# MCU.net
KiCad netlist of a schematic drawn in Altium Designer
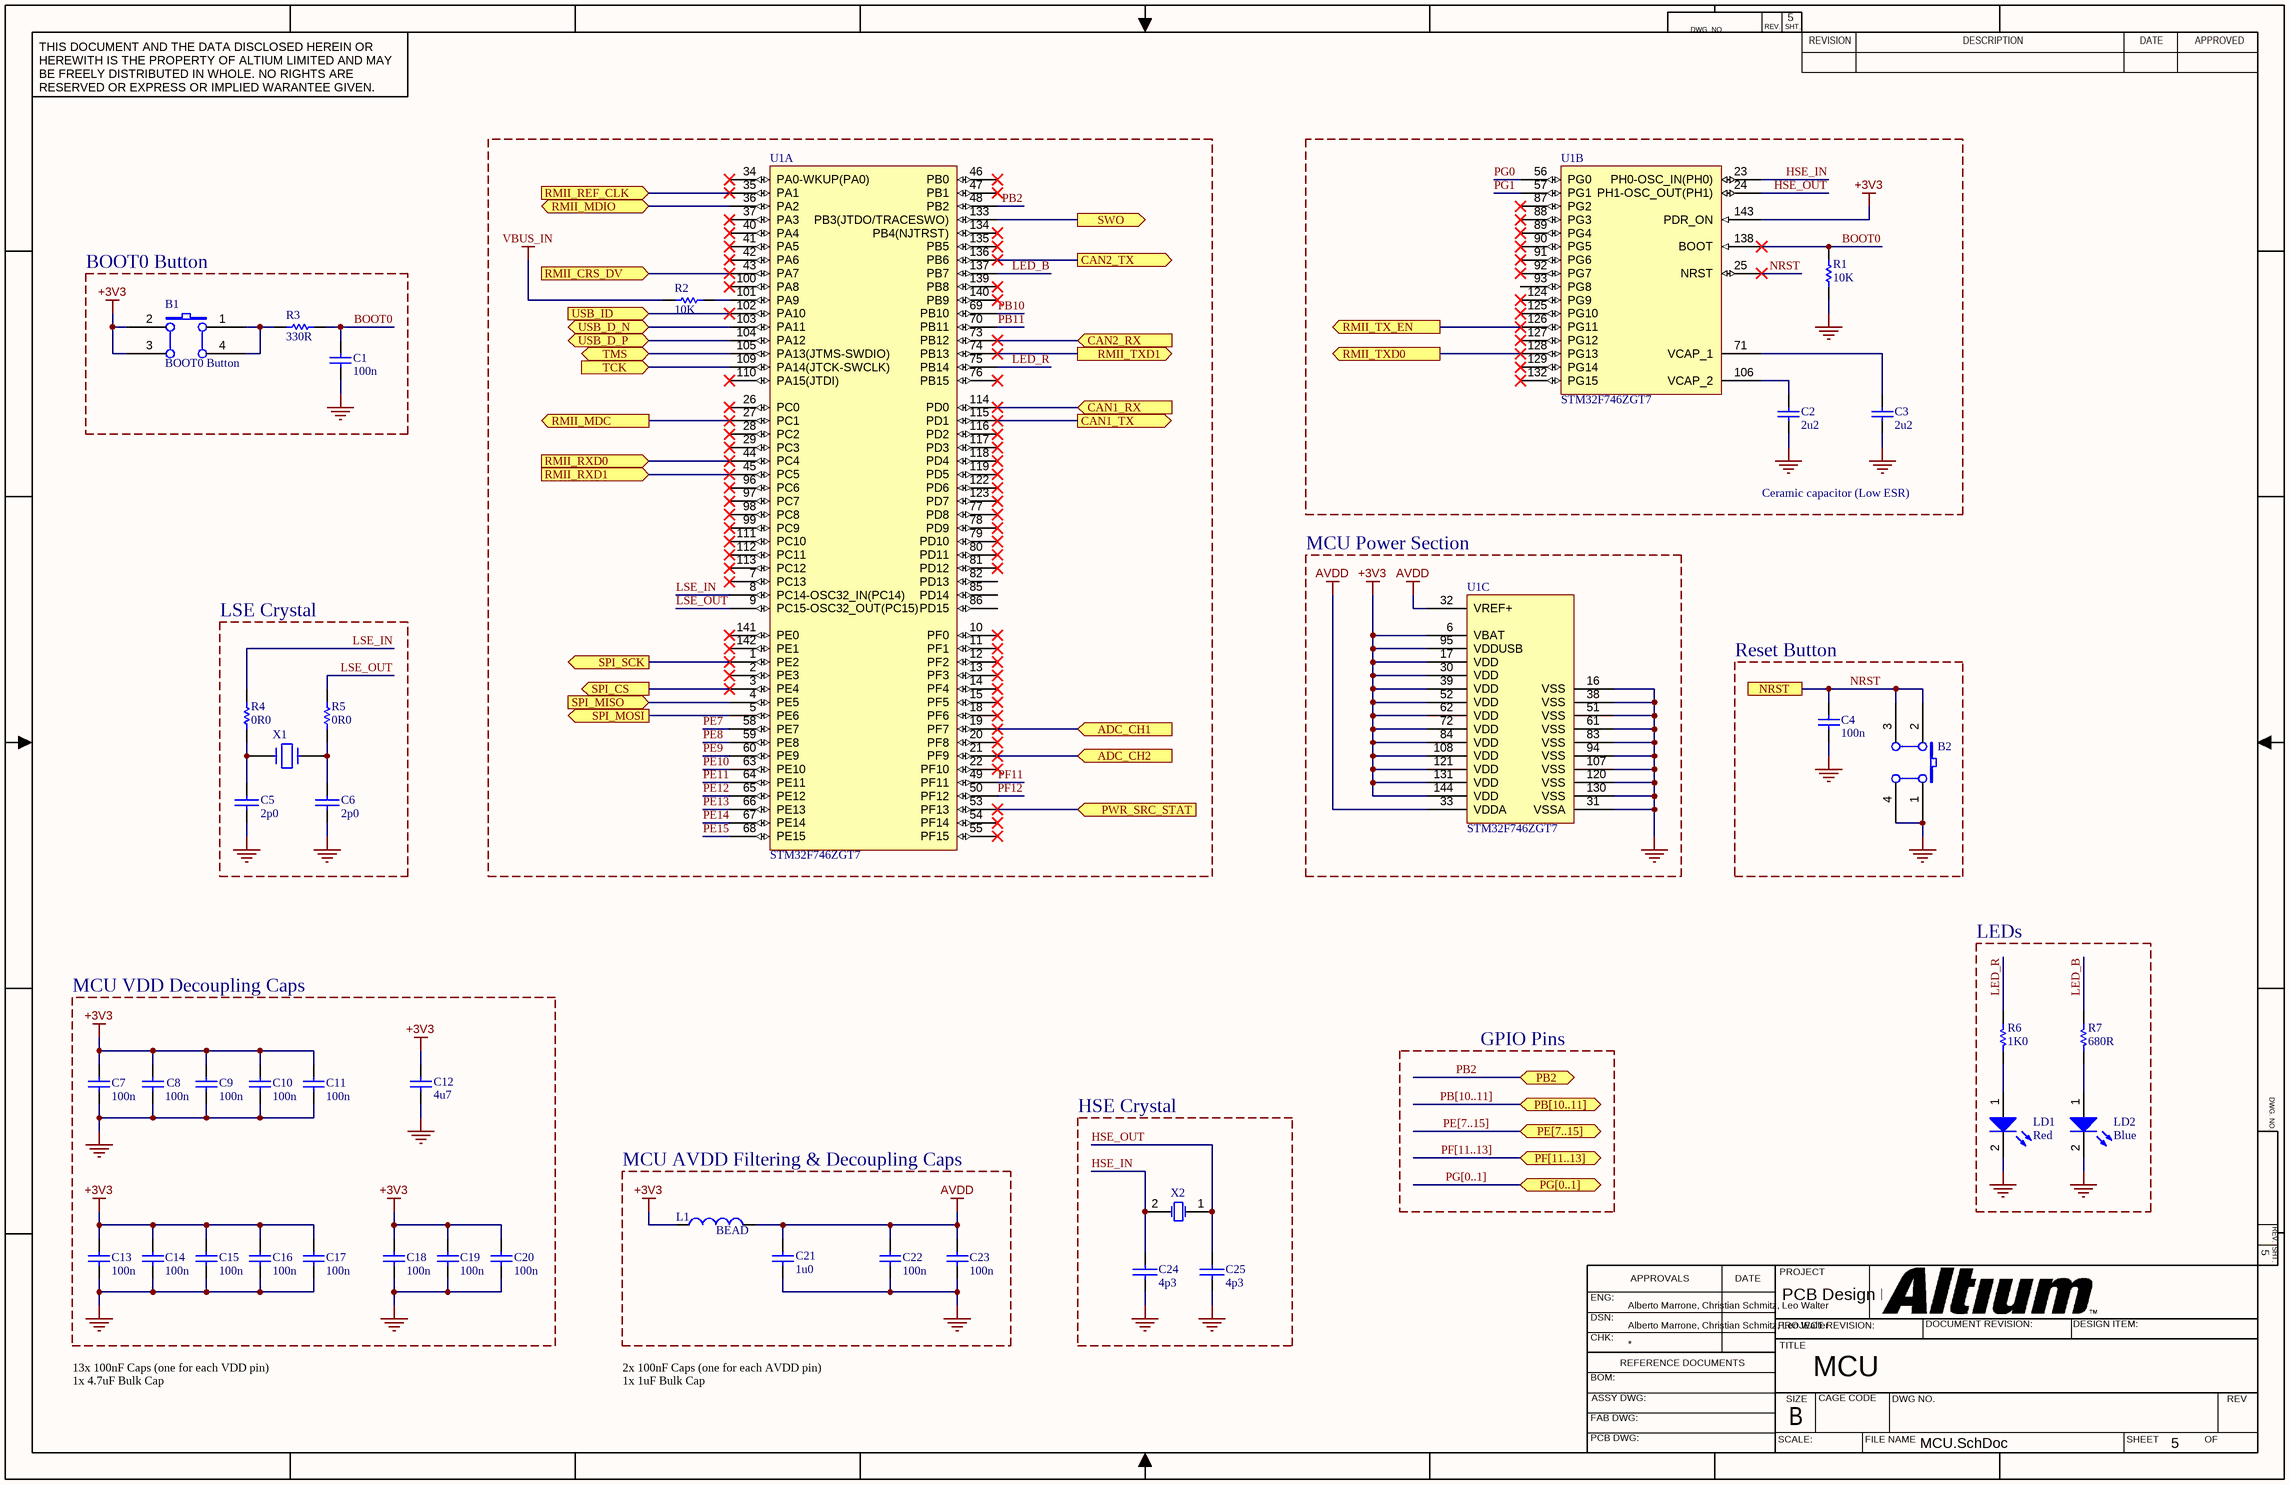
[diagram p0: MCU.SchDoc]

(export (version "E")
  (design (tool "Eeschema 10.0.6"))
  (components
    (comp (ref "B1")
      (value "BOOT0 Button")
      (footprint "PB-6X6mm-Blue")
      (description "SE PUSHBUTTON")
      (libsource (lib "Documents") (part "SW PUSHBUTTON"))
    )
    (comp (ref "B2")
      (value "TS40-66-33-BK-160-SMT-TR")
      (footprint "PB-6X6mm-Black")
      (description "SE PUSHBUTTON")
      (libsource (lib "Documents") (part "SW PUSHBUTTON"))
    )
    (comp (ref "C1")
      (value "100n")
      (footprint "0603C")
      (description "Capacitor")
      (fields (field (name "PUBLISHER") "Altium Limited"))
      (libsource (lib "Miscellaneous Devices") (part "Cap"))
    )
    (comp (ref "C2")
      (value "2u2")
      (footprint "TAN-A")
      (description "Capacitor,2.2uF,16V, X7R,10%,0805,YAGEO")
      (libsource (lib "MCD_TOOLS") (part "Cap_2.2uF_X7R_10%_0805"))
    )
    (comp (ref "C3")
      (value "2u2")
      (footprint "TAN-A")
      (description "Capacitor,2.2uF,16V, X7R,10%,0805,YAGEO")
      (libsource (lib "MCD_TOOLS") (part "Cap_2.2uF_X7R_10%_0805"))
    )
    (comp (ref "C4")
      (value "100n")
      (footprint "0603C")
      (description "Capacitor")
      (fields (field (name "PUBLISHER") "Altium Limited"))
      (libsource (lib "Miscellaneous Devices") (part "Cap"))
    )
    (comp (ref "C5")
      (value "2p0")
      (footprint "0603C")
      (description "Capacitor")
      (libsource (lib "") (part "CAP_1"))
    )
    (comp (ref "C6")
      (value "2p0")
      (footprint "0603C")
      (description "Capacitor")
      (libsource (lib "") (part "CAP_1"))
    )
    (comp (ref "C7")
      (value "100n")
      (footprint "0603C")
      (description "Capacitor")
      (fields (field (name "PUBLISHER") "Altium Limited"))
      (libsource (lib "Miscellaneous Devices") (part "Cap"))
    )
    (comp (ref "C8")
      (value "100n")
      (footprint "0603C")
      (description "Capacitor")
      (fields (field (name "PUBLISHER") "Altium Limited"))
      (libsource (lib "Miscellaneous Devices") (part "Cap"))
    )
    (comp (ref "C9")
      (value "100n")
      (footprint "0603C")
      (description "Capacitor")
      (fields (field (name "PUBLISHER") "Altium Limited"))
      (libsource (lib "Miscellaneous Devices") (part "Cap"))
    )
    (comp (ref "C10")
      (value "100n")
      (footprint "0603C")
      (description "Capacitor")
      (fields (field (name "PUBLISHER") "Altium Limited"))
      (libsource (lib "Miscellaneous Devices") (part "Cap"))
    )
    (comp (ref "C11")
      (value "100n")
      (footprint "0603C")
      (description "Capacitor")
      (fields (field (name "PUBLISHER") "Altium Limited"))
      (libsource (lib "Miscellaneous Devices") (part "Cap"))
    )
    (comp (ref "C12")
      (value "4u7")
      (footprint "0603C")
      (description "Capacitor")
      (fields (field (name "TOLERANCE") "10%"))
      (libsource (lib "MB963_1") (part "CAP SMD 0603  X5R 1µF 25V 10%"))
    )
    (comp (ref "C13")
      (value "100n")
      (footprint "0603C")
      (description "Capacitor")
      (fields (field (name "PUBLISHER") "Altium Limited"))
      (libsource (lib "Miscellaneous Devices") (part "Cap"))
    )
    (comp (ref "C14")
      (value "100n")
      (footprint "0603C")
      (description "Capacitor")
      (fields (field (name "PUBLISHER") "Altium Limited"))
      (libsource (lib "Miscellaneous Devices") (part "Cap"))
    )
    (comp (ref "C15")
      (value "100n")
      (footprint "0603C")
      (description "Capacitor")
      (fields (field (name "PUBLISHER") "Altium Limited"))
      (libsource (lib "Miscellaneous Devices") (part "Cap"))
    )
    (comp (ref "C16")
      (value "100n")
      (footprint "0603C")
      (description "Capacitor")
      (fields (field (name "PUBLISHER") "Altium Limited"))
      (libsource (lib "Miscellaneous Devices") (part "Cap"))
    )
    (comp (ref "C17")
      (value "100n")
      (footprint "0603C")
      (description "Capacitor")
      (fields (field (name "PUBLISHER") "Altium Limited"))
      (libsource (lib "Miscellaneous Devices") (part "Cap"))
    )
    (comp (ref "C18")
      (value "100n")
      (footprint "0603C")
      (description "Capacitor")
      (fields (field (name "PUBLISHER") "Altium Limited"))
      (libsource (lib "Miscellaneous Devices") (part "Cap"))
    )
    (comp (ref "C19")
      (value "100n")
      (footprint "0603C")
      (description "Capacitor")
      (fields (field (name "PUBLISHER") "Altium Limited"))
      (libsource (lib "Miscellaneous Devices") (part "Cap"))
    )
    (comp (ref "C20")
      (value "100n")
      (footprint "0603C")
      (description "Capacitor")
      (fields (field (name "PUBLISHER") "Altium Limited"))
      (libsource (lib "Miscellaneous Devices") (part "Cap"))
    )
    (comp (ref "C21")
      (value "1u0")
      (footprint "0603C")
      (description "Capacitor")
      (fields (field (name "TOLERANCE") "10%"))
      (libsource (lib "MB963_1") (part "CAP SMD 0603  X5R 1µF 25V 10%"))
    )
    (comp (ref "C22")
      (value "100n")
      (footprint "0603C")
      (description "Capacitor")
      (fields (field (name "PUBLISHER") "Altium Limited"))
      (libsource (lib "Miscellaneous Devices") (part "Cap"))
    )
    (comp (ref "C23")
      (value "100n")
      (footprint "0603C")
      (description "Capacitor")
      (fields (field (name "PUBLISHER") "Altium Limited"))
      (libsource (lib "Miscellaneous Devices") (part "Cap"))
    )
    (comp (ref "C24")
      (value "4p3")
      (footprint "0603C")
      (description "Capacitor")
      (libsource (lib "*") (part "CAP"))
    )
    (comp (ref "C25")
      (value "4p3")
      (footprint "0603C")
      (description "Capacitor")
      (libsource (lib "*") (part "CAP"))
    )
    (comp (ref "L1")
      (value "BEAD")
      (footprint "0603L")
      (description "Inductor")
      (fields (field (name "PUBLISHER") "Altium Limited"))
      (libsource (lib "Miscellaneous Devices") (part "Inductor"))
    )
    (comp (ref "LD1")
      (value "Red")
      (footprint "0603D-R")
      (description "Typical RED, GREEN, YELLOW, AMBER GaAs LED")
      (fields (field (name "PUBLISHER") "Altium Limited"))
      (libsource (lib "Miscellaneous Devices") (part "LED2"))
    )
    (comp (ref "LD2")
      (value "Blue")
      (footprint "0603D-B")
      (description "Typical RED, GREEN, YELLOW, AMBER GaAs LED")
      (fields (field (name "PUBLISHER") "Altium Limited"))
      (libsource (lib "Miscellaneous Devices") (part "LED2"))
    )
    (comp (ref "R1")
      (value "10K")
      (footprint "0603R")
      (description "Resistor")
      (fields (field (name "PUBLISHER") "Altium Limited"))
      (libsource (lib "Miscellaneous Devices") (part "res1"))
    )
    (comp (ref "R2")
      (value "10K")
      (footprint "0603R")
      (description "Resistor")
      (fields (field (name "PUBLISHER") "Altium Limited"))
      (libsource (lib "Miscellaneous Devices") (part "res1"))
    )
    (comp (ref "R3")
      (value "330R")
      (footprint "0603R")
      (description "Resistor")
      (fields (field (name "PUBLISHER") "Altium Limited"))
      (libsource (lib "Miscellaneous Devices") (part "Res1"))
    )
    (comp (ref "R4")
      (value "0R0")
      (footprint "0603R")
      (description "Resistor")
      (fields (field (name "PUBLISHER") "Altium Limited"))
      (libsource (lib "Miscellaneous Devices") (part "Res1"))
    )
    (comp (ref "R5")
      (value "0R0")
      (footprint "0603R")
      (description "Resistor")
      (fields (field (name "PUBLISHER") "Altium Limited"))
      (libsource (lib "Miscellaneous Devices") (part "Res1"))
    )
    (comp (ref "R6")
      (value "1K0")
      (footprint "0603R")
      (description "Resistor")
      (fields (field (name "PUBLISHER") "Altium Limited"))
      (libsource (lib "Miscellaneous Devices") (part "Res1"))
    )
    (comp (ref "R7")
      (value "680R")
      (footprint "0603R")
      (description "Resistor")
      (fields (field (name "PUBLISHER") "Altium Limited"))
      (libsource (lib "Miscellaneous Devices") (part "Res1"))
    )
    (comp (ref "U1")
      (value "STM32F746ZGT7")
      (footprint "STM-LQFP144_M")
      (libsource (lib "Altium Content Vault") (part "MC-ARM-STM32F7X6-LQFP144"))
    )
    (comp (ref "X1")
      (value "ABS07-120-32.768KHZ-T")
      (footprint "XTAL_2SM_3R2X1R5")
      (description "Crystal")
      (libsource (lib "MB1167") (part "CRYSTAL_32K"))
    )
    (comp (ref "X2")
      (value "ABM8AAIG-8.000MHz-V2R-T3")
      (footprint "OSC_2SM_3R2x2R5")
      (description "Crystal Oscillator")
      (fields (field (name "PUBLISHER") "Altium Limited"))
      (libsource (lib "MB963_1") (part "XTAL"))
    )
  )
  (nets
    (net (code "2") (name "+3V3") (class "Default")
      (node (ref "B1") (pin "2") (pinfunction "B0_2") (pintype "passive"))
      (node (ref "B1") (pin "3") (pinfunction "B1_3") (pintype "passive"))
      (node (ref "C10") (pin "1") (pinfunction "1_1") (pintype "passive"))
      (node (ref "C11") (pin "1") (pinfunction "1_1") (pintype "passive"))
      (node (ref "C12") (pin "1") (pinfunction "1_1") (pintype "passive"))
      (node (ref "C13") (pin "1") (pinfunction "1_1") (pintype "passive"))
      (node (ref "C14") (pin "1") (pinfunction "1_1") (pintype "passive"))
      (node (ref "C15") (pin "1") (pinfunction "1_1") (pintype "passive"))
      (node (ref "C16") (pin "1") (pinfunction "1_1") (pintype "passive"))
      (node (ref "C17") (pin "1") (pinfunction "1_1") (pintype "passive"))
      (node (ref "C18") (pin "1") (pinfunction "1_1") (pintype "passive"))
      (node (ref "C19") (pin "1") (pinfunction "1_1") (pintype "passive"))
      (node (ref "C20") (pin "1") (pinfunction "1_1") (pintype "passive"))
      (node (ref "C7") (pin "1") (pinfunction "1_1") (pintype "passive"))
      (node (ref "C8") (pin "1") (pinfunction "1_1") (pintype "passive"))
      (node (ref "C9") (pin "1") (pinfunction "1_1") (pintype "passive"))
      (node (ref "L1") (pin "1") (pinfunction "1_1") (pintype "passive"))
      (node (ref "U1") (pin "108") (pinfunction "VDD_108") (pintype "power_in"))
      (node (ref "U1") (pin "121") (pinfunction "VDD_121") (pintype "power_in"))
      (node (ref "U1") (pin "131") (pinfunction "VDD_131") (pintype "power_in"))
      (node (ref "U1") (pin "143") (pinfunction "PDR_ON_143") (pintype "input"))
      (node (ref "U1") (pin "144") (pinfunction "VDD_144") (pintype "power_in"))
      (node (ref "U1") (pin "17") (pinfunction "VDD_17") (pintype "power_in"))
      (node (ref "U1") (pin "30") (pinfunction "VDD_30") (pintype "power_in"))
      (node (ref "U1") (pin "39") (pinfunction "VDD_39") (pintype "power_in"))
      (node (ref "U1") (pin "52") (pinfunction "VDD_52") (pintype "power_in"))
      (node (ref "U1") (pin "6") (pinfunction "VBAT_6") (pintype "power_in"))
      (node (ref "U1") (pin "62") (pinfunction "VDD_62") (pintype "power_in"))
      (node (ref "U1") (pin "72") (pinfunction "VDD_72") (pintype "power_in"))
      (node (ref "U1") (pin "84") (pinfunction "VDD_84") (pintype "power_in"))
      (node (ref "U1") (pin "95") (pinfunction "VDDUSB_95") (pintype "power_in"))
    )
    (net (code "3") (name "/ADC_CH1") (class "Default")
      (node (ref "U1") (pin "19") (pinfunction "PF7_19") (pintype "bidirectional+no_connect"))
    )
    (net (code "4") (name "/ADC_CH2") (class "Default")
      (node (ref "U1") (pin "21") (pinfunction "PF9_21") (pintype "bidirectional+no_connect"))
    )
    (net (code "5") (name "/BOOT0") (class "Default")
      (node (ref "C1") (pin "2") (pinfunction "2_2") (pintype "passive"))
      (node (ref "R1") (pin "1") (pinfunction "1_1") (pintype "passive"))
      (node (ref "R3") (pin "2") (pinfunction "2_2") (pintype "passive"))
      (node (ref "U1") (pin "138") (pinfunction "BOOT_138") (pintype "input"))
    )
    (net (code "6") (name "/CAN1_RX") (class "Default")
      (node (ref "U1") (pin "114") (pinfunction "PD0_114") (pintype "bidirectional+no_connect"))
    )
    (net (code "7") (name "/CAN1_TX") (class "Default")
      (node (ref "U1") (pin "115") (pinfunction "PD1_115") (pintype "bidirectional+no_connect"))
    )
    (net (code "8") (name "/CAN2_RX") (class "Default")
      (node (ref "U1") (pin "73") (pinfunction "PB12_73") (pintype "bidirectional+no_connect"))
    )
    (net (code "9") (name "/CAN2_TX") (class "Default")
      (node (ref "U1") (pin "136") (pinfunction "PB6_136") (pintype "bidirectional+no_connect"))
    )
    (net (code "10") (name "/HSE_IN") (class "Default")
      (node (ref "C24") (pin "1") (pinfunction "1_1") (pintype "passive"))
      (node (ref "U1") (pin "23") (pinfunction "PH0-OSC_IN(PH0)_23") (pintype "bidirectional"))
      (node (ref "X2") (pin "2") (pinfunction "OSC2_2") (pintype "passive"))
    )
    (net (code "11") (name "/HSE_OUT") (class "Default")
      (node (ref "C25") (pin "1") (pinfunction "1_1") (pintype "passive"))
      (node (ref "U1") (pin "24") (pinfunction "PH1-OSC_OUT(PH1)_24") (pintype "bidirectional"))
      (node (ref "X2") (pin "1") (pinfunction "OSC1_1") (pintype "passive"))
    )
    (net (code "12") (name "/LED_B") (class "Default")
      (node (ref "R7") (pin "1") (pinfunction "1_1") (pintype "passive"))
      (node (ref "U1") (pin "137") (pinfunction "PB7_137") (pintype "bidirectional"))
    )
    (net (code "13") (name "/LED_R") (class "Default")
      (node (ref "R6") (pin "1") (pinfunction "1_1") (pintype "passive"))
      (node (ref "U1") (pin "75") (pinfunction "PB14_75") (pintype "bidirectional"))
    )
    (net (code "14") (name "/LSE_IN") (class "Default")
      (node (ref "R4") (pin "2") (pinfunction "2_2") (pintype "passive"))
      (node (ref "U1") (pin "8") (pinfunction "PC14-OSC32_IN(PC14)_8") (pintype "bidirectional"))
    )
    (net (code "15") (name "/LSE_OUT") (class "Default")
      (node (ref "R5") (pin "2") (pinfunction "2_2") (pintype "passive"))
      (node (ref "U1") (pin "9") (pinfunction "PC15-OSC32_OUT(PC15)_9") (pintype "bidirectional"))
    )
    (net (code "16") (name "/NRST") (class "Default")
      (node (ref "B2") (pin "2") (pinfunction "B0_2") (pintype "passive"))
      (node (ref "B2") (pin "3") (pinfunction "B1_3") (pintype "passive"))
      (node (ref "C4") (pin "2") (pinfunction "2_2") (pintype "passive"))
      (node (ref "U1") (pin "25") (pinfunction "NRST_25") (pintype "bidirectional"))
    )
    (net (code "17") (name "/PB2") (class "Default")
      (node (ref "U1") (pin "48") (pinfunction "PB2_48") (pintype "bidirectional"))
    )
    (net (code "18") (name "/PB10") (class "Default")
      (node (ref "U1") (pin "69") (pinfunction "PB10_69") (pintype "bidirectional"))
    )
    (net (code "19") (name "/PB11") (class "Default")
      (node (ref "U1") (pin "70") (pinfunction "PB11_70") (pintype "bidirectional"))
    )
    (net (code "21") (name "/PE7") (class "Default")
      (node (ref "U1") (pin "58") (pinfunction "PE7_58") (pintype "bidirectional"))
    )
    (net (code "22") (name "/PE8") (class "Default")
      (node (ref "U1") (pin "59") (pinfunction "PE8_59") (pintype "bidirectional"))
    )
    (net (code "23") (name "/PE9") (class "Default")
      (node (ref "U1") (pin "60") (pinfunction "PE9_60") (pintype "bidirectional"))
    )
    (net (code "24") (name "/PE10") (class "Default")
      (node (ref "U1") (pin "63") (pinfunction "PE10_63") (pintype "bidirectional"))
    )
    (net (code "25") (name "/PE11") (class "Default")
      (node (ref "U1") (pin "64") (pinfunction "PE11_64") (pintype "bidirectional"))
    )
    (net (code "26") (name "/PE12") (class "Default")
      (node (ref "U1") (pin "65") (pinfunction "PE12_65") (pintype "bidirectional"))
    )
    (net (code "27") (name "/PE13") (class "Default")
      (node (ref "U1") (pin "66") (pinfunction "PE13_66") (pintype "bidirectional"))
    )
    (net (code "28") (name "/PE14") (class "Default")
      (node (ref "U1") (pin "67") (pinfunction "PE14_67") (pintype "bidirectional"))
    )
    (net (code "29") (name "/PE15") (class "Default")
      (node (ref "U1") (pin "68") (pinfunction "PE15_68") (pintype "bidirectional"))
    )
    (net (code "31") (name "/PF11") (class "Default")
      (node (ref "U1") (pin "49") (pinfunction "PF11_49") (pintype "bidirectional"))
    )
    (net (code "32") (name "/PF12") (class "Default")
      (node (ref "U1") (pin "50") (pinfunction "PF12_50") (pintype "bidirectional"))
    )
    (net (code "34") (name "/PG0") (class "Default")
      (node (ref "U1") (pin "56") (pinfunction "PG0_56") (pintype "bidirectional"))
    )
    (net (code "35") (name "/PG1") (class "Default")
      (node (ref "U1") (pin "57") (pinfunction "PG1_57") (pintype "bidirectional"))
    )
    (net (code "37") (name "/PWR_SRC_STAT") (class "Default")
      (node (ref "U1") (pin "53") (pinfunction "PF13_53") (pintype "bidirectional+no_connect"))
    )
    (net (code "38") (name "/RMII_CRS_DV") (class "Default")
      (node (ref "U1") (pin "43") (pinfunction "PA7_43") (pintype "bidirectional+no_connect"))
    )
    (net (code "39") (name "/RMII_MDC") (class "Default")
      (node (ref "U1") (pin "27") (pinfunction "PC1_27") (pintype "bidirectional+no_connect"))
    )
    (net (code "40") (name "/RMII_MDIO") (class "Default")
      (node (ref "U1") (pin "36") (pinfunction "PA2_36") (pintype "bidirectional"))
    )
    (net (code "41") (name "/RMII_REF_CLK") (class "Default")
      (node (ref "U1") (pin "35") (pinfunction "PA1_35") (pintype "bidirectional+no_connect"))
    )
    (net (code "42") (name "/RMII_RXD0") (class "Default")
      (node (ref "U1") (pin "44") (pinfunction "PC4_44") (pintype "bidirectional+no_connect"))
    )
    (net (code "43") (name "/RMII_RXD1") (class "Default")
      (node (ref "U1") (pin "45") (pinfunction "PC5_45") (pintype "bidirectional+no_connect"))
    )
    (net (code "44") (name "/RMII_TXD0") (class "Default")
      (node (ref "U1") (pin "128") (pinfunction "PG13_128") (pintype "bidirectional+no_connect"))
    )
    (net (code "45") (name "/RMII_TXD1") (class "Default")
      (node (ref "U1") (pin "74") (pinfunction "PB13_74") (pintype "bidirectional+no_connect"))
    )
    (net (code "46") (name "/RMII_TX_EN") (class "Default")
      (node (ref "U1") (pin "126") (pinfunction "PG11_126") (pintype "bidirectional+no_connect"))
    )
    (net (code "47") (name "/SPI_CS") (class "Default")
      (node (ref "U1") (pin "3") (pinfunction "PE4_3") (pintype "bidirectional+no_connect"))
    )
    (net (code "48") (name "/SPI_MISO") (class "Default")
      (node (ref "U1") (pin "4") (pinfunction "PE5_4") (pintype "bidirectional"))
    )
    (net (code "49") (name "/SPI_MOSI") (class "Default")
      (node (ref "U1") (pin "5") (pinfunction "PE6_5") (pintype "bidirectional"))
    )
    (net (code "50") (name "/SPI_SCK") (class "Default")
      (node (ref "U1") (pin "1") (pinfunction "PE2_1") (pintype "bidirectional+no_connect"))
    )
    (net (code "51") (name "/SWO") (class "Default")
      (node (ref "U1") (pin "133") (pinfunction "PB3(JTDO/TRACESWO)_133") (pintype "bidirectional"))
    )
    (net (code "52") (name "/TCK") (class "Default")
      (node (ref "U1") (pin "109") (pinfunction "PA14(JTCK-SWCLK)_109") (pintype "bidirectional"))
    )
    (net (code "53") (name "/TMS") (class "Default")
      (node (ref "U1") (pin "105") (pinfunction "PA13(JTMS-SWDIO)_105") (pintype "bidirectional"))
    )
    (net (code "54") (name "/USB_D_N") (class "Default")
      (node (ref "U1") (pin "103") (pinfunction "PA11_103") (pintype "bidirectional"))
    )
    (net (code "55") (name "/USB_D_P") (class "Default")
      (node (ref "U1") (pin "104") (pinfunction "PA12_104") (pintype "bidirectional"))
    )
    (net (code "56") (name "/USB_ID") (class "Default")
      (node (ref "U1") (pin "102") (pinfunction "PA10_102") (pintype "bidirectional+no_connect"))
    )
    (net (code "57") (name "AVDD") (class "Default")
      (node (ref "C21") (pin "1") (pinfunction "1_1") (pintype "passive"))
      (node (ref "C22") (pin "1") (pinfunction "1_1") (pintype "passive"))
      (node (ref "C23") (pin "1") (pinfunction "1_1") (pintype "passive"))
      (node (ref "L1") (pin "2") (pinfunction "2_2") (pintype "passive"))
      (node (ref "U1") (pin "32") (pinfunction "VREF+_32") (pintype "power_in"))
      (node (ref "U1") (pin "33") (pinfunction "VDDA_33") (pintype "power_in"))
    )
    (net (code "58") (name "GND") (class "Default")
      (node (ref "B2") (pin "1") (pinfunction "A0_1") (pintype "passive"))
      (node (ref "B2") (pin "4") (pinfunction "A1_4") (pintype "passive"))
      (node (ref "C1") (pin "1") (pinfunction "1_1") (pintype "passive"))
      (node (ref "C10") (pin "2") (pinfunction "2_2") (pintype "passive"))
      (node (ref "C11") (pin "2") (pinfunction "2_2") (pintype "passive"))
      (node (ref "C12") (pin "2") (pinfunction "2_2") (pintype "passive"))
      (node (ref "C13") (pin "2") (pinfunction "2_2") (pintype "passive"))
      (node (ref "C14") (pin "2") (pinfunction "2_2") (pintype "passive"))
      (node (ref "C15") (pin "2") (pinfunction "2_2") (pintype "passive"))
      (node (ref "C16") (pin "2") (pinfunction "2_2") (pintype "passive"))
      (node (ref "C17") (pin "2") (pinfunction "2_2") (pintype "passive"))
      (node (ref "C18") (pin "2") (pinfunction "2_2") (pintype "passive"))
      (node (ref "C19") (pin "2") (pinfunction "2_2") (pintype "passive"))
      (node (ref "C2") (pin "2") (pinfunction "2_2") (pintype "passive"))
      (node (ref "C20") (pin "2") (pinfunction "2_2") (pintype "passive"))
      (node (ref "C21") (pin "2") (pinfunction "2_2") (pintype "passive"))
      (node (ref "C22") (pin "2") (pinfunction "2_2") (pintype "passive"))
      (node (ref "C23") (pin "2") (pinfunction "2_2") (pintype "passive"))
      (node (ref "C24") (pin "2") (pinfunction "2_2") (pintype "passive"))
      (node (ref "C25") (pin "2") (pinfunction "2_2") (pintype "passive"))
      (node (ref "C3") (pin "2") (pinfunction "2_2") (pintype "passive"))
      (node (ref "C4") (pin "1") (pinfunction "1_1") (pintype "passive"))
      (node (ref "C5") (pin "2") (pinfunction "2_2") (pintype "passive"))
      (node (ref "C6") (pin "2") (pinfunction "2_2") (pintype "passive"))
      (node (ref "C7") (pin "2") (pinfunction "2_2") (pintype "passive"))
      (node (ref "C8") (pin "2") (pinfunction "2_2") (pintype "passive"))
      (node (ref "C9") (pin "2") (pinfunction "2_2") (pintype "passive"))
      (node (ref "LD1") (pin "2") (pinfunction "K_2") (pintype "passive"))
      (node (ref "LD2") (pin "2") (pinfunction "K_2") (pintype "passive"))
      (node (ref "R1") (pin "2") (pinfunction "2_2") (pintype "passive"))
      (node (ref "U1") (pin "107") (pinfunction "VSS_107") (pintype "power_in"))
      (node (ref "U1") (pin "120") (pinfunction "VSS_120") (pintype "power_in"))
      (node (ref "U1") (pin "130") (pinfunction "VSS_130") (pintype "power_in"))
      (node (ref "U1") (pin "16") (pinfunction "VSS_16") (pintype "power_in"))
      (node (ref "U1") (pin "31") (pinfunction "VSSA_31") (pintype "power_in"))
      (node (ref "U1") (pin "38") (pinfunction "VSS_38") (pintype "power_in"))
      (node (ref "U1") (pin "51") (pinfunction "VSS_51") (pintype "power_in"))
      (node (ref "U1") (pin "61") (pinfunction "VSS_61") (pintype "power_in"))
      (node (ref "U1") (pin "83") (pinfunction "VSS_83") (pintype "power_in"))
      (node (ref "U1") (pin "94") (pinfunction "VSS_94") (pintype "power_in"))
    )
    (net (code "59") (name "Net-(B1-A0)") (class "Default")
      (node (ref "B1") (pin "1") (pinfunction "A0_1") (pintype "passive"))
      (node (ref "B1") (pin "4") (pinfunction "A1_4") (pintype "passive"))
      (node (ref "R3") (pin "1") (pinfunction "1_1") (pintype "passive"))
    )
    (net (code "60") (name "Net-(C5-Pad1)") (class "Default")
      (node (ref "C5") (pin "1") (pinfunction "1_1") (pintype "passive"))
      (node (ref "R4") (pin "1") (pinfunction "1_1") (pintype "passive"))
      (node (ref "X1") (pin "2") (pinfunction "2_2") (pintype "passive"))
    )
    (net (code "61") (name "Net-(C6-Pad1)") (class "Default")
      (node (ref "C6") (pin "1") (pinfunction "1_1") (pintype "passive"))
      (node (ref "R5") (pin "1") (pinfunction "1_1") (pintype "passive"))
      (node (ref "X1") (pin "1") (pinfunction "1_1") (pintype "passive"))
    )
    (net (code "62") (name "Net-(LD1-A)") (class "Default")
      (node (ref "LD1") (pin "1") (pinfunction "A_1") (pintype "passive"))
      (node (ref "R6") (pin "2") (pinfunction "2_2") (pintype "passive"))
    )
    (net (code "63") (name "Net-(LD2-A)") (class "Default")
      (node (ref "LD2") (pin "1") (pinfunction "A_1") (pintype "passive"))
      (node (ref "R7") (pin "2") (pinfunction "2_2") (pintype "passive"))
    )
    (net (code "64") (name "Net-(U1A-PA9)") (class "Default")
      (node (ref "R2") (pin "2") (pinfunction "2_2") (pintype "passive"))
      (node (ref "U1") (pin "101") (pinfunction "PA9_101") (pintype "bidirectional"))
    )
    (net (code "65") (name "Net-(U1B-VCAP_1)") (class "Default")
      (node (ref "C3") (pin "1") (pinfunction "1_1") (pintype "passive"))
      (node (ref "U1") (pin "71") (pinfunction "VCAP_1_71") (pintype "passive"))
    )
    (net (code "66") (name "Net-(U1B-VCAP_2)") (class "Default")
      (node (ref "C2") (pin "1") (pinfunction "1_1") (pintype "passive"))
      (node (ref "U1") (pin "106") (pinfunction "VCAP_2_106") (pintype "passive"))
    )
    (net (code "67") (name "VBUS_IN") (class "Default")
      (node (ref "R2") (pin "1") (pinfunction "1_1") (pintype "passive"))
    )
    (net (code "68") (name "unconnected-(U1A-PA0-WKUP(PA0)-Pad34)") (class "Default")
      (node (ref "U1") (pin "34") (pinfunction "PA0-WKUP(PA0)_34") (pintype "bidirectional+no_connect"))
    )
    (net (code "69") (name "unconnected-(U1A-PA3-Pad37)") (class "Default")
      (node (ref "U1") (pin "37") (pinfunction "PA3_37") (pintype "bidirectional+no_connect"))
    )
    (net (code "70") (name "unconnected-(U1A-PA4-Pad40)") (class "Default")
      (node (ref "U1") (pin "40") (pinfunction "PA4_40") (pintype "bidirectional+no_connect"))
    )
    (net (code "71") (name "unconnected-(U1A-PA5-Pad41)") (class "Default")
      (node (ref "U1") (pin "41") (pinfunction "PA5_41") (pintype "bidirectional+no_connect"))
    )
    (net (code "72") (name "unconnected-(U1A-PA6-Pad42)") (class "Default")
      (node (ref "U1") (pin "42") (pinfunction "PA6_42") (pintype "bidirectional+no_connect"))
    )
    (net (code "73") (name "unconnected-(U1A-PA8-Pad100)") (class "Default")
      (node (ref "U1") (pin "100") (pinfunction "PA8_100") (pintype "bidirectional+no_connect"))
    )
    (net (code "74") (name "unconnected-(U1A-PA15(JTDI)-Pad110)") (class "Default")
      (node (ref "U1") (pin "110") (pinfunction "PA15(JTDI)_110") (pintype "bidirectional+no_connect"))
    )
    (net (code "75") (name "unconnected-(U1A-PB0-Pad46)") (class "Default")
      (node (ref "U1") (pin "46") (pinfunction "PB0_46") (pintype "bidirectional+no_connect"))
    )
    (net (code "76") (name "unconnected-(U1A-PB1-Pad47)") (class "Default")
      (node (ref "U1") (pin "47") (pinfunction "PB1_47") (pintype "bidirectional+no_connect"))
    )
    (net (code "77") (name "unconnected-(U1A-PB4(NJTRST)-Pad134)") (class "Default")
      (node (ref "U1") (pin "134") (pinfunction "PB4(NJTRST)_134") (pintype "bidirectional+no_connect"))
    )
    (net (code "78") (name "unconnected-(U1A-PB5-Pad135)") (class "Default")
      (node (ref "U1") (pin "135") (pinfunction "PB5_135") (pintype "bidirectional+no_connect"))
    )
    (net (code "79") (name "unconnected-(U1A-PB8-Pad139)") (class "Default")
      (node (ref "U1") (pin "139") (pinfunction "PB8_139") (pintype "bidirectional+no_connect"))
    )
    (net (code "80") (name "unconnected-(U1A-PB9-Pad140)") (class "Default")
      (node (ref "U1") (pin "140") (pinfunction "PB9_140") (pintype "bidirectional+no_connect"))
    )
    (net (code "81") (name "unconnected-(U1A-PB15-Pad76)") (class "Default")
      (node (ref "U1") (pin "76") (pinfunction "PB15_76") (pintype "bidirectional+no_connect"))
    )
    (net (code "82") (name "unconnected-(U1A-PC0-Pad26)") (class "Default")
      (node (ref "U1") (pin "26") (pinfunction "PC0_26") (pintype "bidirectional+no_connect"))
    )
    (net (code "83") (name "unconnected-(U1A-PC2-Pad28)") (class "Default")
      (node (ref "U1") (pin "28") (pinfunction "PC2_28") (pintype "bidirectional+no_connect"))
    )
    (net (code "84") (name "unconnected-(U1A-PC3-Pad29)") (class "Default")
      (node (ref "U1") (pin "29") (pinfunction "PC3_29") (pintype "bidirectional+no_connect"))
    )
    (net (code "85") (name "unconnected-(U1A-PC6-Pad96)") (class "Default")
      (node (ref "U1") (pin "96") (pinfunction "PC6_96") (pintype "bidirectional+no_connect"))
    )
    (net (code "86") (name "unconnected-(U1A-PC7-Pad97)") (class "Default")
      (node (ref "U1") (pin "97") (pinfunction "PC7_97") (pintype "bidirectional+no_connect"))
    )
    (net (code "87") (name "unconnected-(U1A-PC8-Pad98)") (class "Default")
      (node (ref "U1") (pin "98") (pinfunction "PC8_98") (pintype "bidirectional+no_connect"))
    )
    (net (code "88") (name "unconnected-(U1A-PC9-Pad99)") (class "Default")
      (node (ref "U1") (pin "99") (pinfunction "PC9_99") (pintype "bidirectional+no_connect"))
    )
    (net (code "89") (name "unconnected-(U1A-PC10-Pad111)") (class "Default")
      (node (ref "U1") (pin "111") (pinfunction "PC10_111") (pintype "bidirectional+no_connect"))
    )
    (net (code "90") (name "unconnected-(U1A-PC11-Pad112)") (class "Default")
      (node (ref "U1") (pin "112") (pinfunction "PC11_112") (pintype "bidirectional+no_connect"))
    )
    (net (code "91") (name "unconnected-(U1A-PC12-Pad113)") (class "Default")
      (node (ref "U1") (pin "113") (pinfunction "PC12_113") (pintype "bidirectional+no_connect"))
    )
    (net (code "92") (name "unconnected-(U1A-PC13-Pad7)") (class "Default")
      (node (ref "U1") (pin "7") (pinfunction "PC13_7") (pintype "bidirectional+no_connect"))
    )
    (net (code "93") (name "unconnected-(U1A-PD2-Pad116)") (class "Default")
      (node (ref "U1") (pin "116") (pinfunction "PD2_116") (pintype "bidirectional+no_connect"))
    )
    (net (code "94") (name "unconnected-(U1A-PD3-Pad117)") (class "Default")
      (node (ref "U1") (pin "117") (pinfunction "PD3_117") (pintype "bidirectional+no_connect"))
    )
    (net (code "95") (name "unconnected-(U1A-PD4-Pad118)") (class "Default")
      (node (ref "U1") (pin "118") (pinfunction "PD4_118") (pintype "bidirectional+no_connect"))
    )
    (net (code "96") (name "unconnected-(U1A-PD5-Pad119)") (class "Default")
      (node (ref "U1") (pin "119") (pinfunction "PD5_119") (pintype "bidirectional+no_connect"))
    )
    (net (code "97") (name "unconnected-(U1A-PD6-Pad122)") (class "Default")
      (node (ref "U1") (pin "122") (pinfunction "PD6_122") (pintype "bidirectional+no_connect"))
    )
    (net (code "98") (name "unconnected-(U1A-PD7-Pad123)") (class "Default")
      (node (ref "U1") (pin "123") (pinfunction "PD7_123") (pintype "bidirectional+no_connect"))
    )
    (net (code "99") (name "unconnected-(U1A-PD8-Pad77)") (class "Default")
      (node (ref "U1") (pin "77") (pinfunction "PD8_77") (pintype "bidirectional+no_connect"))
    )
    (net (code "100") (name "unconnected-(U1A-PD9-Pad78)") (class "Default")
      (node (ref "U1") (pin "78") (pinfunction "PD9_78") (pintype "bidirectional+no_connect"))
    )
    (net (code "101") (name "unconnected-(U1A-PD10-Pad79)") (class "Default")
      (node (ref "U1") (pin "79") (pinfunction "PD10_79") (pintype "bidirectional+no_connect"))
    )
    (net (code "102") (name "unconnected-(U1A-PD11-Pad80)") (class "Default")
      (node (ref "U1") (pin "80") (pinfunction "PD11_80") (pintype "bidirectional+no_connect"))
    )
    (net (code "103") (name "unconnected-(U1A-PD12-Pad81)") (class "Default")
      (node (ref "U1") (pin "81") (pinfunction "PD12_81") (pintype "bidirectional+no_connect"))
    )
    (net (code "104") (name "unconnected-(U1A-PD13-Pad82)") (class "Default")
      (node (ref "U1") (pin "82") (pinfunction "PD13_82") (pintype "bidirectional"))
    )
    (net (code "105") (name "unconnected-(U1A-PD14-Pad85)") (class "Default")
      (node (ref "U1") (pin "85") (pinfunction "PD14_85") (pintype "bidirectional"))
    )
    (net (code "106") (name "unconnected-(U1A-PD15-Pad86)") (class "Default")
      (node (ref "U1") (pin "86") (pinfunction "PD15_86") (pintype "bidirectional"))
    )
    (net (code "107") (name "unconnected-(U1A-PE0-Pad141)") (class "Default")
      (node (ref "U1") (pin "141") (pinfunction "PE0_141") (pintype "bidirectional+no_connect"))
    )
    (net (code "108") (name "unconnected-(U1A-PE1-Pad142)") (class "Default")
      (node (ref "U1") (pin "142") (pinfunction "PE1_142") (pintype "bidirectional+no_connect"))
    )
    (net (code "109") (name "unconnected-(U1A-PE3-Pad2)") (class "Default")
      (node (ref "U1") (pin "2") (pinfunction "PE3_2") (pintype "bidirectional+no_connect"))
    )
    (net (code "110") (name "unconnected-(U1A-PF0-Pad10)") (class "Default")
      (node (ref "U1") (pin "10") (pinfunction "PF0_10") (pintype "bidirectional+no_connect"))
    )
    (net (code "111") (name "unconnected-(U1A-PF1-Pad11)") (class "Default")
      (node (ref "U1") (pin "11") (pinfunction "PF1_11") (pintype "bidirectional+no_connect"))
    )
    (net (code "112") (name "unconnected-(U1A-PF2-Pad12)") (class "Default")
      (node (ref "U1") (pin "12") (pinfunction "PF2_12") (pintype "bidirectional+no_connect"))
    )
    (net (code "113") (name "unconnected-(U1A-PF3-Pad13)") (class "Default")
      (node (ref "U1") (pin "13") (pinfunction "PF3_13") (pintype "bidirectional+no_connect"))
    )
    (net (code "114") (name "unconnected-(U1A-PF4-Pad14)") (class "Default")
      (node (ref "U1") (pin "14") (pinfunction "PF4_14") (pintype "bidirectional+no_connect"))
    )
    (net (code "115") (name "unconnected-(U1A-PF5-Pad15)") (class "Default")
      (node (ref "U1") (pin "15") (pinfunction "PF5_15") (pintype "bidirectional+no_connect"))
    )
    (net (code "116") (name "unconnected-(U1A-PF6-Pad18)") (class "Default")
      (node (ref "U1") (pin "18") (pinfunction "PF6_18") (pintype "bidirectional+no_connect"))
    )
    (net (code "117") (name "unconnected-(U1A-PF8-Pad20)") (class "Default")
      (node (ref "U1") (pin "20") (pinfunction "PF8_20") (pintype "bidirectional+no_connect"))
    )
    (net (code "118") (name "unconnected-(U1A-PF10-Pad22)") (class "Default")
      (node (ref "U1") (pin "22") (pinfunction "PF10_22") (pintype "bidirectional+no_connect"))
    )
    (net (code "119") (name "unconnected-(U1A-PF14-Pad54)") (class "Default")
      (node (ref "U1") (pin "54") (pinfunction "PF14_54") (pintype "bidirectional+no_connect"))
    )
    (net (code "120") (name "unconnected-(U1A-PF15-Pad55)") (class "Default")
      (node (ref "U1") (pin "55") (pinfunction "PF15_55") (pintype "bidirectional+no_connect"))
    )
    (net (code "121") (name "unconnected-(U1B-PG2-Pad87)") (class "Default")
      (node (ref "U1") (pin "87") (pinfunction "PG2_87") (pintype "bidirectional+no_connect"))
    )
    (net (code "122") (name "unconnected-(U1B-PG3-Pad88)") (class "Default")
      (node (ref "U1") (pin "88") (pinfunction "PG3_88") (pintype "bidirectional+no_connect"))
    )
    (net (code "123") (name "unconnected-(U1B-PG4-Pad89)") (class "Default")
      (node (ref "U1") (pin "89") (pinfunction "PG4_89") (pintype "bidirectional+no_connect"))
    )
    (net (code "124") (name "unconnected-(U1B-PG5-Pad90)") (class "Default")
      (node (ref "U1") (pin "90") (pinfunction "PG5_90") (pintype "bidirectional+no_connect"))
    )
    (net (code "125") (name "unconnected-(U1B-PG6-Pad91)") (class "Default")
      (node (ref "U1") (pin "91") (pinfunction "PG6_91") (pintype "bidirectional+no_connect"))
    )
    (net (code "126") (name "unconnected-(U1B-PG7-Pad92)") (class "Default")
      (node (ref "U1") (pin "92") (pinfunction "PG7_92") (pintype "bidirectional+no_connect"))
    )
    (net (code "127") (name "unconnected-(U1B-PG8-Pad93)") (class "Default")
      (node (ref "U1") (pin "93") (pinfunction "PG8_93") (pintype "bidirectional"))
    )
    (net (code "128") (name "unconnected-(U1B-PG9-Pad124)") (class "Default")
      (node (ref "U1") (pin "124") (pinfunction "PG9_124") (pintype "bidirectional+no_connect"))
    )
    (net (code "129") (name "unconnected-(U1B-PG10-Pad125)") (class "Default")
      (node (ref "U1") (pin "125") (pinfunction "PG10_125") (pintype "bidirectional+no_connect"))
    )
    (net (code "130") (name "unconnected-(U1B-PG12-Pad127)") (class "Default")
      (node (ref "U1") (pin "127") (pinfunction "PG12_127") (pintype "bidirectional+no_connect"))
    )
    (net (code "131") (name "unconnected-(U1B-PG14-Pad129)") (class "Default")
      (node (ref "U1") (pin "129") (pinfunction "PG14_129") (pintype "bidirectional+no_connect"))
    )
    (net (code "132") (name "unconnected-(U1B-PG15-Pad132)") (class "Default")
      (node (ref "U1") (pin "132") (pinfunction "PG15_132") (pintype "bidirectional+no_connect"))
    )
  )
)
